# dac_7.net
KiCad netlist of a schematic drawn in EAGLE
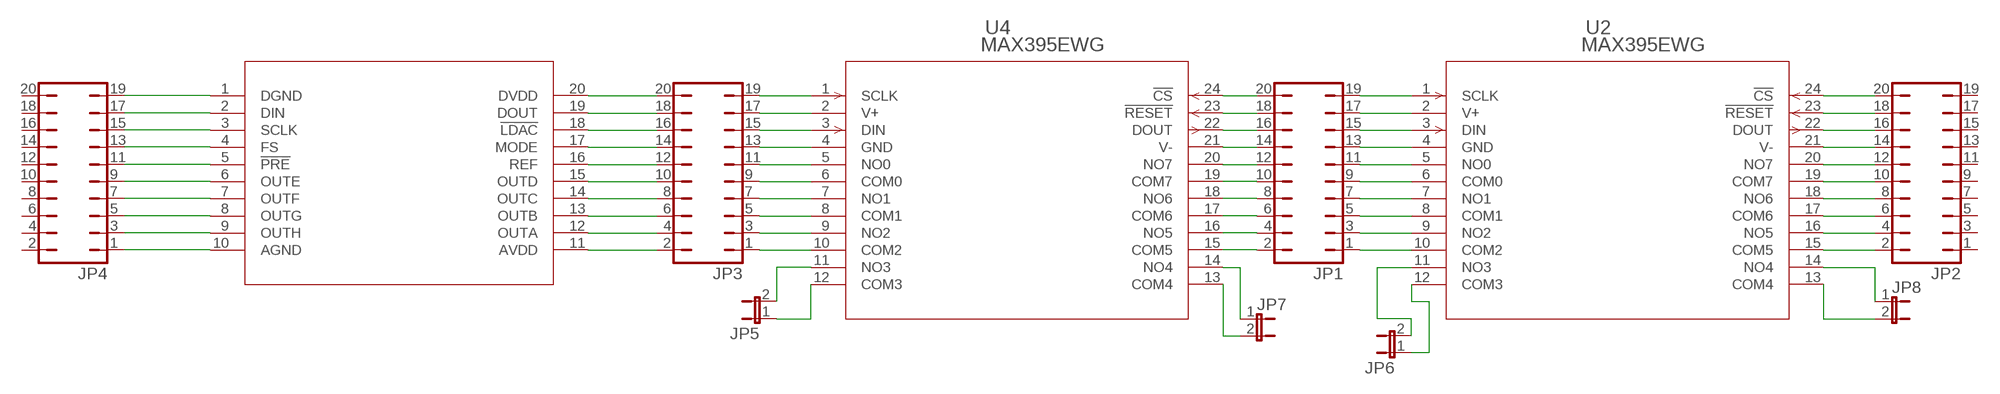
[diagram p0: schematic, sheet 1]

(export (version "E")
  (design (tool "Eeschema 10.0.6"))
  (components
    (comp (ref "JP1")
      (value "JP10Q")
      (footprint "eagle-import:JP10Q")
      (libsource (lib "eagle-import") (part "JP10Q"))
    )
    (comp (ref "JP2")
      (value "JP10Q")
      (footprint "eagle-import:JP10Q")
      (libsource (lib "eagle-import") (part "JP10Q"))
    )
    (comp (ref "JP3")
      (value "JP10Q")
      (footprint "eagle-import:JP10Q")
      (libsource (lib "eagle-import") (part "JP10Q"))
    )
    (comp (ref "JP4")
      (value "JP10Q")
      (footprint "eagle-import:JP10Q")
      (libsource (lib "eagle-import") (part "JP10Q"))
    )
    (comp (ref "JP5")
      (value "JP1E")
      (footprint "eagle-import:JP1")
      (libsource (lib "eagle-import") (part "JP1E"))
    )
    (comp (ref "JP6")
      (value "JP1E")
      (footprint "eagle-import:JP1")
      (libsource (lib "eagle-import") (part "JP1E"))
    )
    (comp (ref "JP7")
      (value "JP1E")
      (footprint "eagle-import:JP1")
      (libsource (lib "eagle-import") (part "JP1E"))
    )
    (comp (ref "JP8")
      (value "JP1E")
      (footprint "eagle-import:JP1")
      (libsource (lib "eagle-import") (part "JP1E"))
    )
    (comp (ref "U1")
      (value "TLV5610_DW_20")
      (footprint "eagle-import:DW20")
      (libsource (lib "eagle-import") (part "TLV5610_DW_20"))
    )
    (comp (ref "U2")
      (value "MAX395EWG")
      (footprint "eagle-import:21-0042B_24")
      (fields (field (name "MANUFACTURER_PART_NUMBER") "max395ewg"))
      (libsource (lib "eagle-import") (part "MAX395EWG"))
    )
    (comp (ref "U4")
      (value "MAX395EWG")
      (footprint "eagle-import:21-0042B_24")
      (fields (field (name "MANUFACTURER_PART_NUMBER") "max395ewg"))
      (libsource (lib "eagle-import") (part "MAX395EWG"))
    )
  )
  (nets
    (net (code "1") (name "Net-(U1-AGND)") (class "Default")
      (node (ref "JP4") (pin "1") (pinfunction "1_1") (pintype "passive"))
      (node (ref "U1") (pin "10") (pinfunction "AGND_10") (pintype "power_in"))
    )
    (net (code "2") (name "Net-(U1-AVDD)") (class "Default")
      (node (ref "JP3") (pin "2") (pinfunction "2_2") (pintype "passive"))
      (node (ref "U1") (pin "11") (pinfunction "AVDD_11") (pintype "power_in"))
    )
    (net (code "3") (name "Net-(U1-DGND)") (class "Default")
      (node (ref "JP4") (pin "19") (pinfunction "19_19") (pintype "passive"))
      (node (ref "U1") (pin "1") (pinfunction "DGND_1") (pintype "power_in"))
    )
    (net (code "4") (name "Net-(U1-DIN)") (class "Default")
      (node (ref "JP4") (pin "17") (pinfunction "17_17") (pintype "passive"))
      (node (ref "U1") (pin "2") (pinfunction "DIN_2") (pintype "input"))
    )
    (net (code "5") (name "Net-(U1-DOUT)") (class "Default")
      (node (ref "JP3") (pin "18") (pinfunction "18_18") (pintype "passive"))
      (node (ref "U1") (pin "19") (pinfunction "DOUT_19") (pintype "output"))
    )
    (net (code "6") (name "Net-(U1-DVDD)") (class "Default")
      (node (ref "JP3") (pin "20") (pinfunction "20_20") (pintype "passive"))
      (node (ref "U1") (pin "20") (pinfunction "DVDD_20") (pintype "power_in"))
    )
    (net (code "7") (name "Net-(U1-FS)") (class "Default")
      (node (ref "JP4") (pin "13") (pinfunction "13_13") (pintype "passive"))
      (node (ref "U1") (pin "4") (pinfunction "FS_4") (pintype "input"))
    )
    (net (code "8") (name "Net-(U1-MODE)") (class "Default")
      (node (ref "JP3") (pin "14") (pinfunction "14_14") (pintype "passive"))
      (node (ref "U1") (pin "17") (pinfunction "MODE_17") (pintype "input"))
    )
    (net (code "9") (name "Net-(U1-OUTA)") (class "Default")
      (node (ref "JP3") (pin "4") (pinfunction "4_4") (pintype "passive"))
      (node (ref "U1") (pin "12") (pinfunction "OUTA_12") (pintype "output"))
    )
    (net (code "10") (name "Net-(U1-OUTB)") (class "Default")
      (node (ref "JP3") (pin "6") (pinfunction "6_6") (pintype "passive"))
      (node (ref "U1") (pin "13") (pinfunction "OUTB_13") (pintype "output"))
    )
    (net (code "11") (name "Net-(U1-OUTC)") (class "Default")
      (node (ref "JP3") (pin "8") (pinfunction "8_8") (pintype "passive"))
      (node (ref "U1") (pin "14") (pinfunction "OUTC_14") (pintype "output"))
    )
    (net (code "12") (name "Net-(U1-OUTD)") (class "Default")
      (node (ref "JP3") (pin "10") (pinfunction "10_10") (pintype "passive"))
      (node (ref "U1") (pin "15") (pinfunction "OUTD_15") (pintype "output"))
    )
    (net (code "13") (name "Net-(U1-OUTE)") (class "Default")
      (node (ref "JP4") (pin "9") (pinfunction "9_9") (pintype "passive"))
      (node (ref "U1") (pin "6") (pinfunction "OUTE_6") (pintype "output"))
    )
    (net (code "14") (name "Net-(U1-OUTF)") (class "Default")
      (node (ref "JP4") (pin "7") (pinfunction "7_7") (pintype "passive"))
      (node (ref "U1") (pin "7") (pinfunction "OUTF_7") (pintype "output"))
    )
    (net (code "15") (name "Net-(U1-OUTG)") (class "Default")
      (node (ref "JP4") (pin "5") (pinfunction "5_5") (pintype "passive"))
      (node (ref "U1") (pin "8") (pinfunction "OUTG_8") (pintype "output"))
    )
    (net (code "16") (name "Net-(U1-OUTH)") (class "Default")
      (node (ref "JP4") (pin "3") (pinfunction "3_3") (pintype "passive"))
      (node (ref "U1") (pin "9") (pinfunction "OUTH_9") (pintype "output"))
    )
    (net (code "17") (name "Net-(U1-REF)") (class "Default")
      (node (ref "JP3") (pin "12") (pinfunction "12_12") (pintype "passive"))
      (node (ref "U1") (pin "16") (pinfunction "REF_16") (pintype "input"))
    )
    (net (code "18") (name "Net-(U1-SCLK)") (class "Default")
      (node (ref "JP4") (pin "15") (pinfunction "15_15") (pintype "passive"))
      (node (ref "U1") (pin "3") (pinfunction "SCLK_3") (pintype "input"))
    )
    (net (code "19") (name "Net-(U1-~{LDAC})") (class "Default")
      (node (ref "JP3") (pin "16") (pinfunction "16_16") (pintype "passive"))
      (node (ref "U1") (pin "18") (pinfunction "~{LDAC}_18") (pintype "input"))
    )
    (net (code "20") (name "Net-(U1-~{PRE})") (class "Default")
      (node (ref "JP4") (pin "11") (pinfunction "11_11") (pintype "passive"))
      (node (ref "U1") (pin "5") (pinfunction "~{PRE}_5") (pintype "input"))
    )
    (net (code "21") (name "Net-(U2-COM0)") (class "Default")
      (node (ref "JP1") (pin "9") (pinfunction "9_9") (pintype "passive"))
      (node (ref "U2") (pin "6") (pinfunction "COM0_6") (pintype "passive"))
    )
    (net (code "22") (name "Net-(U2-COM1)") (class "Default")
      (node (ref "JP1") (pin "5") (pinfunction "5_5") (pintype "passive"))
      (node (ref "U2") (pin "8") (pinfunction "COM1_8") (pintype "passive"))
    )
    (net (code "23") (name "Net-(U2-COM2)") (class "Default")
      (node (ref "JP1") (pin "1") (pinfunction "1_1") (pintype "passive"))
      (node (ref "U2") (pin "10") (pinfunction "COM2_10") (pintype "passive"))
    )
    (net (code "24") (name "Net-(U2-COM3)") (class "Default")
      (node (ref "JP6") (pin "1") (pinfunction "1_1") (pintype "passive"))
      (node (ref "U2") (pin "12") (pinfunction "COM3_12") (pintype "passive"))
    )
    (net (code "25") (name "Net-(U2-COM4)") (class "Default")
      (node (ref "JP8") (pin "2") (pinfunction "2_2") (pintype "passive"))
      (node (ref "U2") (pin "13") (pinfunction "COM4_13") (pintype "passive"))
    )
    (net (code "26") (name "Net-(U2-COM5)") (class "Default")
      (node (ref "JP2") (pin "2") (pinfunction "2_2") (pintype "passive"))
      (node (ref "U2") (pin "15") (pinfunction "COM5_15") (pintype "passive"))
    )
    (net (code "27") (name "Net-(U2-COM6)") (class "Default")
      (node (ref "JP2") (pin "6") (pinfunction "6_6") (pintype "passive"))
      (node (ref "U2") (pin "17") (pinfunction "COM6_17") (pintype "passive"))
    )
    (net (code "28") (name "Net-(U2-COM7)") (class "Default")
      (node (ref "JP2") (pin "10") (pinfunction "10_10") (pintype "passive"))
      (node (ref "U2") (pin "19") (pinfunction "COM7_19") (pintype "passive"))
    )
    (net (code "29") (name "Net-(U2-DIN)") (class "Default")
      (node (ref "JP1") (pin "15") (pinfunction "15_15") (pintype "passive"))
      (node (ref "U2") (pin "3") (pinfunction "DIN_3") (pintype "input"))
    )
    (net (code "30") (name "Net-(U2-DOUT)") (class "Default")
      (node (ref "JP2") (pin "16") (pinfunction "16_16") (pintype "passive"))
      (node (ref "U2") (pin "22") (pinfunction "DOUT_22") (pintype "output"))
    )
    (net (code "31") (name "Net-(U2-GND)") (class "Default")
      (node (ref "JP1") (pin "13") (pinfunction "13_13") (pintype "passive"))
      (node (ref "U2") (pin "4") (pinfunction "GND_4") (pintype "power_in"))
    )
    (net (code "32") (name "Net-(U2-NO0)") (class "Default")
      (node (ref "JP1") (pin "11") (pinfunction "11_11") (pintype "passive"))
      (node (ref "U2") (pin "5") (pinfunction "NO0_5") (pintype "passive"))
    )
    (net (code "33") (name "Net-(U2-NO1)") (class "Default")
      (node (ref "JP1") (pin "7") (pinfunction "7_7") (pintype "passive"))
      (node (ref "U2") (pin "7") (pinfunction "NO1_7") (pintype "passive"))
    )
    (net (code "34") (name "Net-(U2-NO2)") (class "Default")
      (node (ref "JP1") (pin "3") (pinfunction "3_3") (pintype "passive"))
      (node (ref "U2") (pin "9") (pinfunction "NO2_9") (pintype "passive"))
    )
    (net (code "35") (name "Net-(U2-NO3)") (class "Default")
      (node (ref "JP6") (pin "2") (pinfunction "2_2") (pintype "passive"))
      (node (ref "U2") (pin "11") (pinfunction "NO3_11") (pintype "passive"))
    )
    (net (code "36") (name "Net-(U2-NO4)") (class "Default")
      (node (ref "JP8") (pin "1") (pinfunction "1_1") (pintype "passive"))
      (node (ref "U2") (pin "14") (pinfunction "NO4_14") (pintype "passive"))
    )
    (net (code "37") (name "Net-(U2-NO5)") (class "Default")
      (node (ref "JP2") (pin "4") (pinfunction "4_4") (pintype "passive"))
      (node (ref "U2") (pin "16") (pinfunction "NO5_16") (pintype "passive"))
    )
    (net (code "38") (name "Net-(U2-NO6)") (class "Default")
      (node (ref "JP2") (pin "8") (pinfunction "8_8") (pintype "passive"))
      (node (ref "U2") (pin "18") (pinfunction "NO6_18") (pintype "passive"))
    )
    (net (code "39") (name "Net-(U2-NO7)") (class "Default")
      (node (ref "JP2") (pin "12") (pinfunction "12_12") (pintype "passive"))
      (node (ref "U2") (pin "20") (pinfunction "NO7_20") (pintype "passive"))
    )
    (net (code "40") (name "Net-(U2-SCLK)") (class "Default")
      (node (ref "JP1") (pin "19") (pinfunction "19_19") (pintype "passive"))
      (node (ref "U2") (pin "1") (pinfunction "SCLK_1") (pintype "input"))
    )
    (net (code "41") (name "Net-(U2-V+)") (class "Default")
      (node (ref "JP1") (pin "17") (pinfunction "17_17") (pintype "passive"))
      (node (ref "U2") (pin "2") (pinfunction "V+_2") (pintype "power_in"))
    )
    (net (code "42") (name "Net-(U2-V-)") (class "Default")
      (node (ref "JP2") (pin "14") (pinfunction "14_14") (pintype "passive"))
      (node (ref "U2") (pin "21") (pinfunction "V-_21") (pintype "power_in"))
    )
    (net (code "43") (name "Net-(U2-~{CS})") (class "Default")
      (node (ref "JP2") (pin "20") (pinfunction "20_20") (pintype "passive"))
      (node (ref "U2") (pin "24") (pinfunction "~{CS}_24") (pintype "input"))
    )
    (net (code "44") (name "Net-(U2-~{RESET})") (class "Default")
      (node (ref "JP2") (pin "18") (pinfunction "18_18") (pintype "passive"))
      (node (ref "U2") (pin "23") (pinfunction "~{RESET}_23") (pintype "input"))
    )
    (net (code "45") (name "Net-(U4-COM0)") (class "Default")
      (node (ref "JP3") (pin "9") (pinfunction "9_9") (pintype "passive"))
      (node (ref "U4") (pin "6") (pinfunction "COM0_6") (pintype "passive"))
    )
    (net (code "46") (name "Net-(U4-COM1)") (class "Default")
      (node (ref "JP3") (pin "5") (pinfunction "5_5") (pintype "passive"))
      (node (ref "U4") (pin "8") (pinfunction "COM1_8") (pintype "passive"))
    )
    (net (code "47") (name "Net-(U4-COM2)") (class "Default")
      (node (ref "JP3") (pin "1") (pinfunction "1_1") (pintype "passive"))
      (node (ref "U4") (pin "10") (pinfunction "COM2_10") (pintype "passive"))
    )
    (net (code "48") (name "Net-(U4-COM3)") (class "Default")
      (node (ref "JP5") (pin "1") (pinfunction "1_1") (pintype "passive"))
      (node (ref "U4") (pin "12") (pinfunction "COM3_12") (pintype "passive"))
    )
    (net (code "49") (name "Net-(U4-COM4)") (class "Default")
      (node (ref "JP7") (pin "2") (pinfunction "2_2") (pintype "passive"))
      (node (ref "U4") (pin "13") (pinfunction "COM4_13") (pintype "passive"))
    )
    (net (code "50") (name "Net-(U4-COM5)") (class "Default")
      (node (ref "JP1") (pin "2") (pinfunction "2_2") (pintype "passive"))
      (node (ref "U4") (pin "15") (pinfunction "COM5_15") (pintype "passive"))
    )
    (net (code "51") (name "Net-(U4-COM6)") (class "Default")
      (node (ref "JP1") (pin "6") (pinfunction "6_6") (pintype "passive"))
      (node (ref "U4") (pin "17") (pinfunction "COM6_17") (pintype "passive"))
    )
    (net (code "52") (name "Net-(U4-COM7)") (class "Default")
      (node (ref "JP1") (pin "10") (pinfunction "10_10") (pintype "passive"))
      (node (ref "U4") (pin "19") (pinfunction "COM7_19") (pintype "passive"))
    )
    (net (code "53") (name "Net-(U4-DIN)") (class "Default")
      (node (ref "JP3") (pin "15") (pinfunction "15_15") (pintype "passive"))
      (node (ref "U4") (pin "3") (pinfunction "DIN_3") (pintype "input"))
    )
    (net (code "54") (name "Net-(U4-DOUT)") (class "Default")
      (node (ref "JP1") (pin "16") (pinfunction "16_16") (pintype "passive"))
      (node (ref "U4") (pin "22") (pinfunction "DOUT_22") (pintype "output"))
    )
    (net (code "55") (name "Net-(U4-GND)") (class "Default")
      (node (ref "JP3") (pin "13") (pinfunction "13_13") (pintype "passive"))
      (node (ref "U4") (pin "4") (pinfunction "GND_4") (pintype "power_in"))
    )
    (net (code "56") (name "Net-(U4-NO0)") (class "Default")
      (node (ref "JP3") (pin "11") (pinfunction "11_11") (pintype "passive"))
      (node (ref "U4") (pin "5") (pinfunction "NO0_5") (pintype "passive"))
    )
    (net (code "57") (name "Net-(U4-NO1)") (class "Default")
      (node (ref "JP3") (pin "7") (pinfunction "7_7") (pintype "passive"))
      (node (ref "U4") (pin "7") (pinfunction "NO1_7") (pintype "passive"))
    )
    (net (code "58") (name "Net-(U4-NO2)") (class "Default")
      (node (ref "JP3") (pin "3") (pinfunction "3_3") (pintype "passive"))
      (node (ref "U4") (pin "9") (pinfunction "NO2_9") (pintype "passive"))
    )
    (net (code "59") (name "Net-(U4-NO3)") (class "Default")
      (node (ref "JP5") (pin "2") (pinfunction "2_2") (pintype "passive"))
      (node (ref "U4") (pin "11") (pinfunction "NO3_11") (pintype "passive"))
    )
    (net (code "60") (name "Net-(U4-NO4)") (class "Default")
      (node (ref "JP7") (pin "1") (pinfunction "1_1") (pintype "passive"))
      (node (ref "U4") (pin "14") (pinfunction "NO4_14") (pintype "passive"))
    )
    (net (code "61") (name "Net-(U4-NO5)") (class "Default")
      (node (ref "JP1") (pin "4") (pinfunction "4_4") (pintype "passive"))
      (node (ref "U4") (pin "16") (pinfunction "NO5_16") (pintype "passive"))
    )
    (net (code "62") (name "Net-(U4-NO6)") (class "Default")
      (node (ref "JP1") (pin "8") (pinfunction "8_8") (pintype "passive"))
      (node (ref "U4") (pin "18") (pinfunction "NO6_18") (pintype "passive"))
    )
    (net (code "63") (name "Net-(U4-NO7)") (class "Default")
      (node (ref "JP1") (pin "12") (pinfunction "12_12") (pintype "passive"))
      (node (ref "U4") (pin "20") (pinfunction "NO7_20") (pintype "passive"))
    )
    (net (code "64") (name "Net-(U4-SCLK)") (class "Default")
      (node (ref "JP3") (pin "19") (pinfunction "19_19") (pintype "passive"))
      (node (ref "U4") (pin "1") (pinfunction "SCLK_1") (pintype "input"))
    )
    (net (code "65") (name "Net-(U4-V+)") (class "Default")
      (node (ref "JP3") (pin "17") (pinfunction "17_17") (pintype "passive"))
      (node (ref "U4") (pin "2") (pinfunction "V+_2") (pintype "power_in"))
    )
    (net (code "66") (name "Net-(U4-V-)") (class "Default")
      (node (ref "JP1") (pin "14") (pinfunction "14_14") (pintype "passive"))
      (node (ref "U4") (pin "21") (pinfunction "V-_21") (pintype "power_in"))
    )
    (net (code "67") (name "Net-(U4-~{CS})") (class "Default")
      (node (ref "JP1") (pin "20") (pinfunction "20_20") (pintype "passive"))
      (node (ref "U4") (pin "24") (pinfunction "~{CS}_24") (pintype "input"))
    )
    (net (code "68") (name "Net-(U4-~{RESET})") (class "Default")
      (node (ref "JP1") (pin "18") (pinfunction "18_18") (pintype "passive"))
      (node (ref "U4") (pin "23") (pinfunction "~{RESET}_23") (pintype "input"))
    )
    (net (code "69") (name "unconnected-(JP2-Pad1)") (class "Default")
      (node (ref "JP2") (pin "1") (pinfunction "1_1") (pintype "passive"))
    )
    (net (code "70") (name "unconnected-(JP2-Pad3)") (class "Default")
      (node (ref "JP2") (pin "3") (pinfunction "3_3") (pintype "passive"))
    )
    (net (code "71") (name "unconnected-(JP2-Pad5)") (class "Default")
      (node (ref "JP2") (pin "5") (pinfunction "5_5") (pintype "passive"))
    )
    (net (code "72") (name "unconnected-(JP2-Pad7)") (class "Default")
      (node (ref "JP2") (pin "7") (pinfunction "7_7") (pintype "passive"))
    )
    (net (code "73") (name "unconnected-(JP2-Pad9)") (class "Default")
      (node (ref "JP2") (pin "9") (pinfunction "9_9") (pintype "passive"))
    )
    (net (code "74") (name "unconnected-(JP2-Pad11)") (class "Default")
      (node (ref "JP2") (pin "11") (pinfunction "11_11") (pintype "passive"))
    )
    (net (code "75") (name "unconnected-(JP2-Pad13)") (class "Default")
      (node (ref "JP2") (pin "13") (pinfunction "13_13") (pintype "passive"))
    )
    (net (code "76") (name "unconnected-(JP2-Pad15)") (class "Default")
      (node (ref "JP2") (pin "15") (pinfunction "15_15") (pintype "passive"))
    )
    (net (code "77") (name "unconnected-(JP2-Pad17)") (class "Default")
      (node (ref "JP2") (pin "17") (pinfunction "17_17") (pintype "passive"))
    )
    (net (code "78") (name "unconnected-(JP2-Pad19)") (class "Default")
      (node (ref "JP2") (pin "19") (pinfunction "19_19") (pintype "passive"))
    )
    (net (code "79") (name "unconnected-(JP4-Pad2)") (class "Default")
      (node (ref "JP4") (pin "2") (pinfunction "2_2") (pintype "passive"))
    )
    (net (code "80") (name "unconnected-(JP4-Pad4)") (class "Default")
      (node (ref "JP4") (pin "4") (pinfunction "4_4") (pintype "passive"))
    )
    (net (code "81") (name "unconnected-(JP4-Pad6)") (class "Default")
      (node (ref "JP4") (pin "6") (pinfunction "6_6") (pintype "passive"))
    )
    (net (code "82") (name "unconnected-(JP4-Pad8)") (class "Default")
      (node (ref "JP4") (pin "8") (pinfunction "8_8") (pintype "passive"))
    )
    (net (code "83") (name "unconnected-(JP4-Pad10)") (class "Default")
      (node (ref "JP4") (pin "10") (pinfunction "10_10") (pintype "passive"))
    )
    (net (code "84") (name "unconnected-(JP4-Pad12)") (class "Default")
      (node (ref "JP4") (pin "12") (pinfunction "12_12") (pintype "passive"))
    )
    (net (code "85") (name "unconnected-(JP4-Pad14)") (class "Default")
      (node (ref "JP4") (pin "14") (pinfunction "14_14") (pintype "passive"))
    )
    (net (code "86") (name "unconnected-(JP4-Pad16)") (class "Default")
      (node (ref "JP4") (pin "16") (pinfunction "16_16") (pintype "passive"))
    )
    (net (code "87") (name "unconnected-(JP4-Pad18)") (class "Default")
      (node (ref "JP4") (pin "18") (pinfunction "18_18") (pintype "passive"))
    )
    (net (code "88") (name "unconnected-(JP4-Pad20)") (class "Default")
      (node (ref "JP4") (pin "20") (pinfunction "20_20") (pintype "passive"))
    )
  )
)
